# FPGA_CFG.net
KiCad netlist of a schematic drawn in Altium Designer
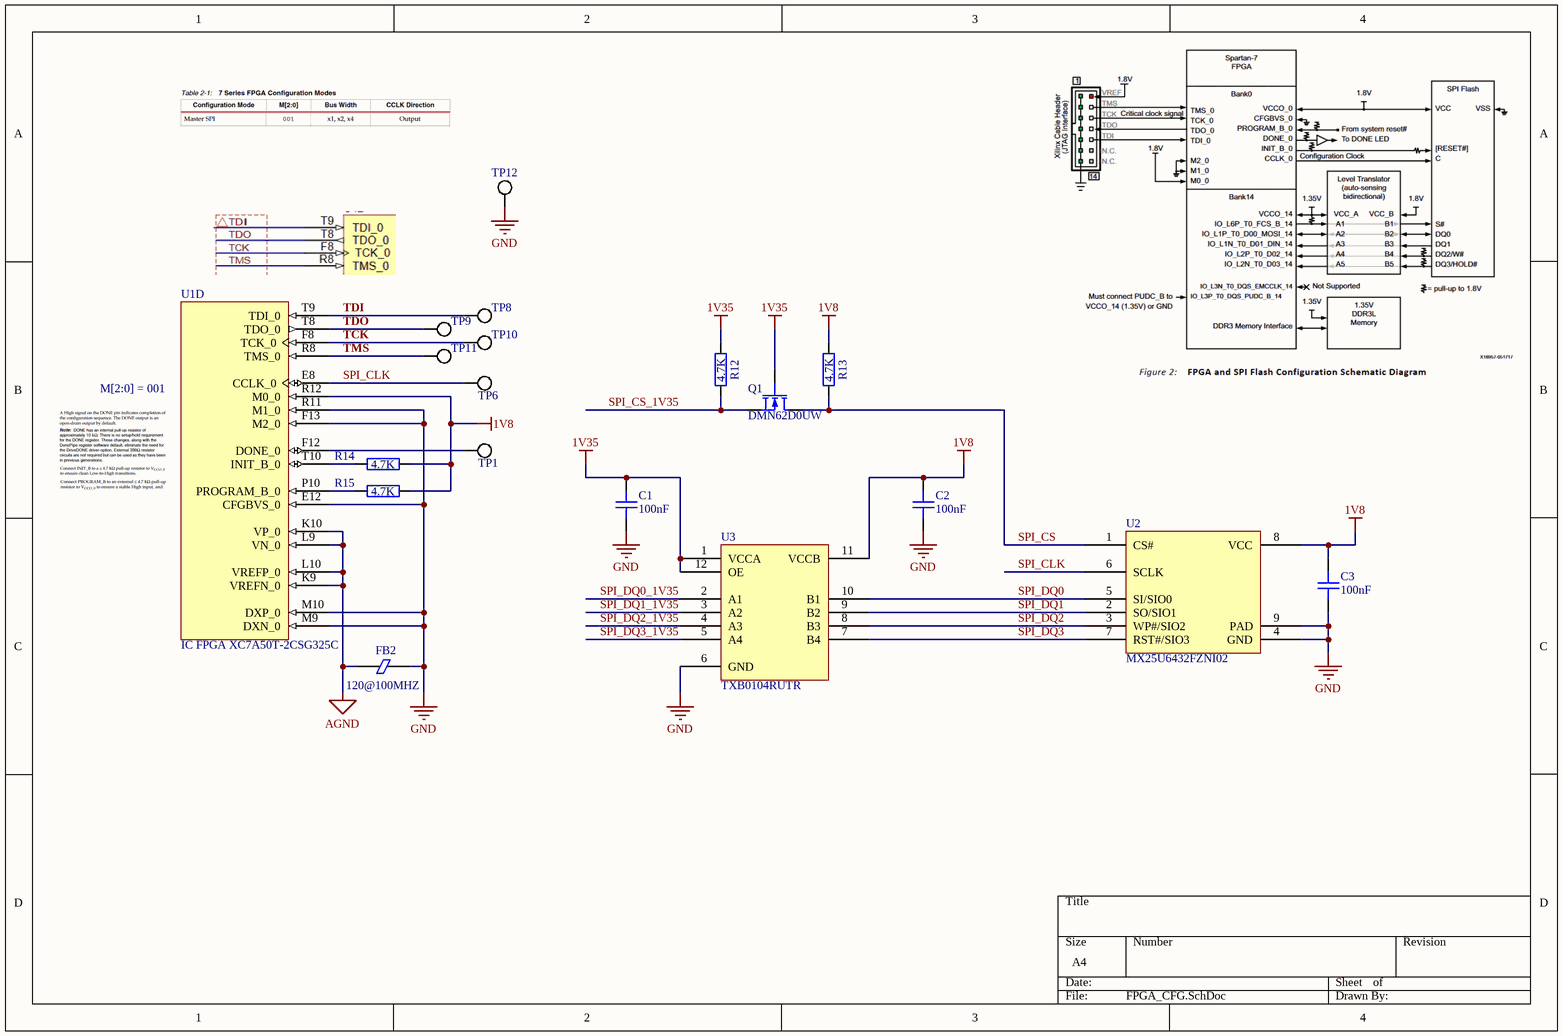
[diagram p0: FPGA_CFG.SchDoc]

(export (version "E")
  (design (tool "Eeschema 10.0.6"))
  (components
    (comp (ref "C1")
      (value "100nF")
      (footprint "GEN_C_0402")
      (libsource (lib "DSO") (part "CAP 100nF 16V X7R 0402"))
    )
    (comp (ref "C2")
      (value "100nF")
      (footprint "GEN_C_0402")
      (libsource (lib "DSO") (part "CAP 100nF 16V X7R 0402"))
    )
    (comp (ref "C3")
      (value "100nF")
      (footprint "GEN_C_0402")
      (libsource (lib "DSO") (part "CAP 100nF 16V X7R 0402"))
    )
    (comp (ref "FB2")
      (value "120@100MHZ")
      (footprint "GEN_R_0402")
      (libsource (lib "DSO") (part "FERRITE BEAD 120 OHM 0402"))
    )
    (comp (ref "Q1")
      (value "DMN62D0UW")
      (footprint "GEN_SOT_323")
      (libsource (lib "DSO") (part "NMOS DMN62D0UW"))
    )
    (comp (ref "R12")
      (value "4.7K")
      (footprint "GEN_R_0201")
      (fields (field (name "TOLERANCE") "1%"))
      (libsource (lib "") (part "RES 4.7K OHM 1% 1/20W 0201_1"))
    )
    (comp (ref "R13")
      (value "4.7K")
      (footprint "GEN_R_0201")
      (fields (field (name "TOLERANCE") "1%"))
      (libsource (lib "") (part "RES 4.7K OHM 1% 1/20W 0201_1"))
    )
    (comp (ref "R14")
      (value "4.7K")
      (footprint "GEN_R_0201")
      (fields (field (name "TOLERANCE") "1%"))
      (libsource (lib "DSO") (part "RES 4.7K OHM 1% 1/20W 0201"))
    )
    (comp (ref "R15")
      (value "4.7K")
      (footprint "GEN_R_0201")
      (fields (field (name "TOLERANCE") "1%"))
      (libsource (lib "DSO") (part "RES 4.7K OHM 1% 1/20W 0201"))
    )
    (comp (ref "TP1") (value "PCB") (footprint "GEN_TP_PCB") (libsource (lib "DSO") (part "TP PCB 1mm")))
    (comp (ref "TP6") (value "PCB") (footprint "GEN_TP_PCB") (libsource (lib "DSO") (part "TP PCB 1mm")))
    (comp (ref "TP8") (value "PCB") (footprint "GEN_TP_PCB") (libsource (lib "DSO") (part "TP PCB 1mm")))
    (comp (ref "TP9") (value "PCB") (footprint "GEN_TP_PCB") (libsource (lib "DSO") (part "TP PCB 1mm")))
    (comp (ref "TP10") (value "PCB") (footprint "GEN_TP_PCB") (libsource (lib "DSO") (part "TP PCB 1mm")))
    (comp (ref "TP11") (value "PCB") (footprint "GEN_TP_PCB") (libsource (lib "DSO") (part "TP PCB 1mm")))
    (comp (ref "TP12") (value "PCB") (footprint "GEN_TP_PCB") (libsource (lib "DSO") (part "TP PCB 1mm")))
    (comp (ref "U1")
      (value "IC FPGA XC7A50T-2CSG325C")
      (footprint "XILINX_XC7A50T-2CSG325C")
      (description "Artix-7 FPGA, 150 User I/Os, 4 GTP, 324-Ball BGA, Speed Grade 2, Commercial Grade, Pb-Free")
      (fields (field (name "MANUFACTURER") "Xilinx") (field (name "PARTNUMBER") "XC7A35T-2CSG325C"))
      (libsource (lib "DSO") (part "IC FPGA XC7A50T-2CSG325C"))
    )
    (comp (ref "U2")
      (value "MX25U6432FZNI02")
      (footprint "MX_WSON8")
      (libsource (lib "DSO") (part "IC FLASH MX25U6432FZNI02"))
    )
    (comp (ref "U3")
      (value "TXB0104RUTR")
      (footprint "TI_UQFN_RUT0012A")
      (libsource (lib "DSO") (part "IC TRNSLTR TXB0104RUTR"))
    )
  )
  (nets
    (net (code "1") (name "/SPI_CLK") (class "Default")
      (node (ref "TP6") (pin "1") (pinfunction "1_1") (pintype "passive"))
      (node (ref "U1") (pin "E8") (pinfunction "CCLK_0_E8") (pintype "bidirectional"))
      (node (ref "U2") (pin "6") (pinfunction "SCLK_6") (pintype "passive"))
    )
    (net (code "2") (name "/SPI_CS") (class "Default")
      (node (ref "Q1") (pin "1") (pinfunction "D_1") (pintype "passive"))
      (node (ref "R13") (pin "1") (pinfunction "1_1") (pintype "passive"))
      (node (ref "U2") (pin "1") (pinfunction "CS#_1") (pintype "passive"))
    )
    (net (code "3") (name "/SPI_CS_1V35") (class "Default")
      (node (ref "Q1") (pin "3") (pinfunction "S_3") (pintype "passive"))
      (node (ref "R12") (pin "1") (pinfunction "1_1") (pintype "passive"))
    )
    (net (code "4") (name "/SPI_DQ0") (class "Default")
      (node (ref "U2") (pin "5") (pinfunction "SI/SIO0_5") (pintype "passive"))
      (node (ref "U3") (pin "10") (pinfunction "B1_10") (pintype "passive"))
    )
    (net (code "5") (name "/SPI_DQ0_1V35") (class "Default")
      (node (ref "U3") (pin "2") (pinfunction "A1_2") (pintype "passive"))
    )
    (net (code "6") (name "/SPI_DQ1") (class "Default")
      (node (ref "U2") (pin "2") (pinfunction "SO/SIO1_2") (pintype "passive"))
      (node (ref "U3") (pin "9") (pinfunction "B2_9") (pintype "passive"))
    )
    (net (code "7") (name "/SPI_DQ1_1V35") (class "Default")
      (node (ref "U3") (pin "3") (pinfunction "A2_3") (pintype "passive"))
    )
    (net (code "8") (name "/SPI_DQ2") (class "Default")
      (node (ref "U2") (pin "3") (pinfunction "WP#/SIO2_3") (pintype "passive"))
      (node (ref "U3") (pin "8") (pinfunction "B3_8") (pintype "passive"))
    )
    (net (code "9") (name "/SPI_DQ2_1V35") (class "Default")
      (node (ref "U3") (pin "4") (pinfunction "A3_4") (pintype "passive"))
    )
    (net (code "10") (name "/SPI_DQ3") (class "Default")
      (node (ref "U2") (pin "7") (pinfunction "RST#/SIO3_7") (pintype "passive"))
      (node (ref "U3") (pin "7") (pinfunction "B4_7") (pintype "passive"))
    )
    (net (code "11") (name "/SPI_DQ3_1V35") (class "Default")
      (node (ref "U3") (pin "5") (pinfunction "A4_5") (pintype "passive"))
    )
    (net (code "12") (name "/TCK") (class "Default")
      (node (ref "TP10") (pin "1") (pinfunction "1_1") (pintype "passive"))
      (node (ref "U1") (pin "F8") (pinfunction "TCK_0_F8") (pintype "input"))
    )
    (net (code "13") (name "/TDI") (class "Default")
      (node (ref "TP8") (pin "1") (pinfunction "1_1") (pintype "passive"))
      (node (ref "U1") (pin "T9") (pinfunction "TDI_0_T9") (pintype "input"))
    )
    (net (code "14") (name "/TDO") (class "Default")
      (node (ref "TP9") (pin "1") (pinfunction "1_1") (pintype "passive"))
      (node (ref "U1") (pin "T8") (pinfunction "TDO_0_T8") (pintype "output"))
    )
    (net (code "15") (name "/TMS") (class "Default")
      (node (ref "TP11") (pin "1") (pinfunction "1_1") (pintype "passive"))
      (node (ref "U1") (pin "R8") (pinfunction "TMS_0_R8") (pintype "input"))
    )
    (net (code "16") (name "1V8") (class "Default")
      (node (ref "C2") (pin "1") (pinfunction "1_1") (pintype "passive"))
      (node (ref "C3") (pin "1") (pinfunction "1_1") (pintype "passive"))
      (node (ref "R13") (pin "2") (pinfunction "2_2") (pintype "passive"))
      (node (ref "R14") (pin "2") (pinfunction "2_2") (pintype "passive"))
      (node (ref "R15") (pin "2") (pinfunction "2_2") (pintype "passive"))
      (node (ref "U1") (pin "R12") (pinfunction "M0_0_R12") (pintype "input"))
      (node (ref "U2") (pin "8") (pinfunction "VCC_8") (pintype "passive"))
      (node (ref "U3") (pin "11") (pinfunction "VCCB_11") (pintype "passive"))
    )
    (net (code "17") (name "1V35") (class "Default")
      (node (ref "C1") (pin "1") (pinfunction "1_1") (pintype "passive"))
      (node (ref "Q1") (pin "2") (pinfunction "G_2") (pintype "passive"))
      (node (ref "R12") (pin "2") (pinfunction "2_2") (pintype "passive"))
      (node (ref "U3") (pin "1") (pinfunction "VCCA_1") (pintype "passive"))
      (node (ref "U3") (pin "12") (pinfunction "OE_12") (pintype "passive"))
    )
    (net (code "18") (name "AGND") (class "Default")
      (node (ref "FB2") (pin "1") (pinfunction "1_1") (pintype "passive"))
      (node (ref "U1") (pin "K10") (pinfunction "VP_0_K10") (pintype "input"))
      (node (ref "U1") (pin "K9") (pinfunction "VREFN_0_K9") (pintype "input"))
      (node (ref "U1") (pin "L10") (pinfunction "VREFP_0_L10") (pintype "input"))
      (node (ref "U1") (pin "L9") (pinfunction "VN_0_L9") (pintype "input"))
    )
    (net (code "19") (name "GND") (class "Default")
      (node (ref "C1") (pin "2") (pinfunction "2_2") (pintype "passive"))
      (node (ref "C2") (pin "2") (pinfunction "2_2") (pintype "passive"))
      (node (ref "C3") (pin "2") (pinfunction "2_2") (pintype "passive"))
      (node (ref "FB2") (pin "2") (pinfunction "2_2") (pintype "passive"))
      (node (ref "TP12") (pin "1") (pinfunction "1_1") (pintype "passive"))
      (node (ref "U1") (pin "E12") (pinfunction "CFGBVS_0_E12") (pintype "input"))
      (node (ref "U1") (pin "F13") (pinfunction "M2_0_F13") (pintype "input"))
      (node (ref "U1") (pin "M10") (pinfunction "DXP_0_M10") (pintype "input"))
      (node (ref "U1") (pin "M9") (pinfunction "DXN_0_M9") (pintype "input"))
      (node (ref "U1") (pin "R11") (pinfunction "M1_0_R11") (pintype "input"))
      (node (ref "U2") (pin "4") (pinfunction "GND_4") (pintype "passive"))
      (node (ref "U2") (pin "9") (pinfunction "PAD_9") (pintype "passive"))
      (node (ref "U3") (pin "6") (pinfunction "GND_6") (pintype "passive"))
    )
    (net (code "20") (name "Net-(U1D-DONE_0)") (class "Default")
      (node (ref "TP1") (pin "1") (pinfunction "1_1") (pintype "passive"))
      (node (ref "U1") (pin "F12") (pinfunction "DONE_0_F12") (pintype "bidirectional"))
    )
    (net (code "21") (name "Net-(U1D-INIT_B_0)") (class "Default")
      (node (ref "R14") (pin "1") (pinfunction "1_1") (pintype "passive"))
      (node (ref "U1") (pin "T10") (pinfunction "INIT_B_0_T10") (pintype "bidirectional"))
    )
    (net (code "22") (name "Net-(U1D-PROGRAM_B_0)") (class "Default")
      (node (ref "R15") (pin "1") (pinfunction "1_1") (pintype "passive"))
      (node (ref "U1") (pin "P10") (pinfunction "PROGRAM_B_0_P10") (pintype "input"))
    )
  )
)
